# USB.net
KiCad netlist of a schematic drawn in Altium Designer
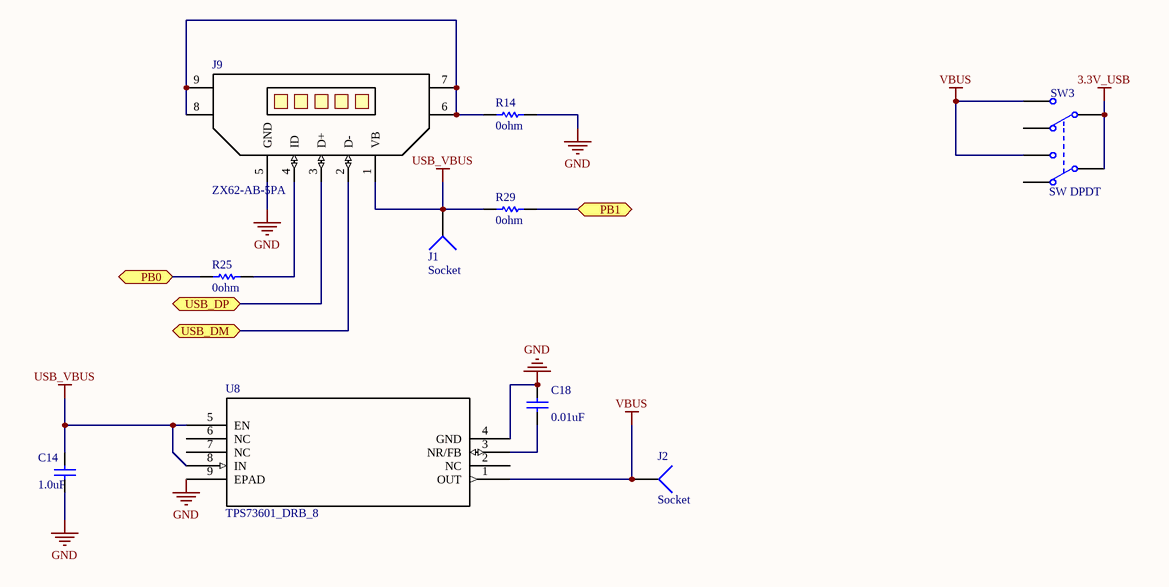
[diagram p0: USB.SchDoc]

(export (version "E")
  (design (tool "Eeschema 10.0.6"))
  (components
    (comp (ref "C14")
      (value "1.0uF")
      (footprint "C0805")
      (description "Capacitor (Semiconductor SIM Model)")
      (fields (field (name "PUBLISHER") "Altium Limited"))
      (libsource (lib "Miscellaneous Devices") (part "Cap Semi"))
    )
    (comp (ref "C18")
      (value "0.01uF")
      (footprint "C0805")
      (description "Capacitor (Semiconductor SIM Model)")
      (fields (field (name "PUBLISHER") "Altium Limited"))
      (libsource (lib "Miscellaneous Devices") (part "Cap Semi"))
    )
    (comp (ref "J1")
      (value "Socket")
      (footprint "PIN1")
      (fields (field (name "PUBLISHER") "Altium Limited"))
      (libsource (lib "Miscellaneous Connectors") (part "Socket"))
    )
    (comp (ref "J2")
      (value "Socket")
      (footprint "PIN1")
      (fields (field (name "PUBLISHER") "Altium Limited"))
      (libsource (lib "Miscellaneous Connectors") (part "Socket"))
    )
    (comp (ref "J9")
      (value "ZX62-AB-5PA")
      (footprint "TM4C_Launchpad:ZX62-AB-5PA")
      (libsource (lib "TM4C_Launchpad") (part "ZX62-AB-5PA"))
    )
    (comp (ref "R14")
      (value "0ohm")
      (footprint "ERA-0805")
      (fields (field (name "PUBLISHER") "Altium Limited"))
      (libsource (lib "Panasonic Resistor") (part "ERAS"))
    )
    (comp (ref "R25")
      (value "0ohm")
      (footprint "ERA-0805")
      (fields (field (name "PUBLISHER") "Altium Limited"))
      (libsource (lib "Panasonic Resistor") (part "ERAS"))
    )
    (comp (ref "R29")
      (value "0ohm")
      (footprint "ERA-0805")
      (fields (field (name "PUBLISHER") "Altium Limited"))
      (libsource (lib "Panasonic Resistor") (part "ERAS"))
    )
    (comp (ref "SW3")
      (value "SW DPDT")
      (footprint "TM4C_Launchpad:JS202011SCQN")
      (description "Switch")
      (fields (field (name "PUBLISHER") "Altium Limited"))
      (libsource (lib "Miscellaneous Devices") (part "SW DPDT"))
    )
    (comp (ref "U8")
      (value "TPS73601_DRB_8")
      (footprint "DRB8_1P75X1P5")
      (description "Imported")
      (fields
        (field (name "MANUFACTURER_PART_NUMBER") "tps73601_drb_8")
        (field (name "GENERIC_PART_NUMBER") "TPS73601")
      )
      (libsource (lib "TM4C_Launchpad") (part "TPS73601_DRB_8"))
    )
  )
  (nets
    (net (code "1") (name "/PB0") (class "Default")
      (node (ref "R25") (pin "1") (pinfunction "1_1") (pintype "passive"))
    )
    (net (code "2") (name "/PB1") (class "Default")
      (node (ref "R29") (pin "2") (pinfunction "2_2") (pintype "passive"))
    )
    (net (code "3") (name "/USB_DM") (class "Default")
      (node (ref "J9") (pin "2") (pinfunction "D-_2") (pintype "bidirectional"))
    )
    (net (code "4") (name "/USB_DP") (class "Default")
      (node (ref "J9") (pin "3") (pinfunction "D+_3") (pintype "bidirectional"))
    )
    (net (code "5") (name "3.3V_USB") (class "Default")
      (node (ref "SW3") (pin "1") (pinfunction "COMMON1_1") (pintype "passive"))
      (node (ref "SW3") (pin "5") (pinfunction "COMMON2_5") (pintype "passive"))
    )
    (net (code "6") (name "GND") (class "Default")
      (node (ref "C14") (pin "1") (pinfunction "1_1") (pintype "passive"))
      (node (ref "C18") (pin "2") (pinfunction "2_2") (pintype "passive"))
      (node (ref "J9") (pin "5") (pinfunction "GND_5") (pintype "power_in"))
      (node (ref "R14") (pin "2") (pinfunction "2_2") (pintype "passive"))
      (node (ref "U8") (pin "4") (pinfunction "GND_4") (pintype "power_in"))
      (node (ref "U8") (pin "9") (pinfunction "EPAD_9") (pintype "passive"))
    )
    (net (code "7") (name "Net-(J9-ID)") (class "Default")
      (node (ref "J9") (pin "4") (pinfunction "ID_4") (pintype "bidirectional"))
      (node (ref "R25") (pin "2") (pinfunction "2_2") (pintype "passive"))
    )
    (net (code "8") (name "Net-(J9-Pad6)") (class "Default")
      (node (ref "J9") (pin "6") (pintype "power_in"))
      (node (ref "J9") (pin "7") (pintype "power_in"))
      (node (ref "J9") (pin "8") (pintype "power_in"))
      (node (ref "J9") (pin "9") (pintype "power_in"))
      (node (ref "R14") (pin "1") (pinfunction "1_1") (pintype "passive"))
    )
    (net (code "9") (name "Net-(U8-NR{slash}FB)") (class "Default")
      (node (ref "C18") (pin "1") (pinfunction "1_1") (pintype "passive"))
      (node (ref "U8") (pin "3") (pinfunction "NR/FB_3") (pintype "bidirectional"))
    )
    (net (code "10") (name "USB_VBUS") (class "Default")
      (node (ref "C14") (pin "2") (pinfunction "2_2") (pintype "passive"))
      (node (ref "J1") (pin "1") (pinfunction "1_1") (pintype "passive"))
      (node (ref "J9") (pin "1") (pinfunction "VB_1") (pintype "power_in"))
      (node (ref "R29") (pin "1") (pinfunction "1_1") (pintype "passive"))
      (node (ref "U8") (pin "5") (pinfunction "EN_5") (pintype "passive"))
      (node (ref "U8") (pin "8") (pinfunction "IN_8") (pintype "input"))
    )
    (net (code "11") (name "VBUS") (class "Default")
      (node (ref "J2") (pin "1") (pinfunction "1_1") (pintype "passive"))
      (node (ref "SW3") (pin "3") (pinfunction "NO1_3") (pintype "passive"))
      (node (ref "SW3") (pin "6") (pinfunction "NO2_6") (pintype "passive"))
      (node (ref "U8") (pin "1") (pinfunction "OUT_1") (pintype "output"))
    )
    (net (code "12") (name "unconnected-(SW3-NC1-Pad2)") (class "Default")
      (node (ref "SW3") (pin "2") (pinfunction "NC1_2") (pintype "passive"))
    )
    (net (code "13") (name "unconnected-(SW3-NC2-Pad4)") (class "Default")
      (node (ref "SW3") (pin "4") (pinfunction "NC2_4") (pintype "passive"))
    )
    (net (code "14") (name "unconnected-(U8-NC-Pad2)") (class "Default")
      (node (ref "U8") (pin "2") (pinfunction "NC_2") (pintype "passive"))
    )
    (net (code "15") (name "unconnected-(U8-NC-Pad6)") (class "Default")
      (node (ref "U8") (pin "6") (pinfunction "NC_6") (pintype "passive"))
    )
    (net (code "16") (name "unconnected-(U8-NC-Pad7)") (class "Default")
      (node (ref "U8") (pin "7") (pinfunction "NC_7") (pintype "passive"))
    )
  )
)
